# Electrical_Channels.net
KiCad netlist of a schematic drawn in Altium Designer
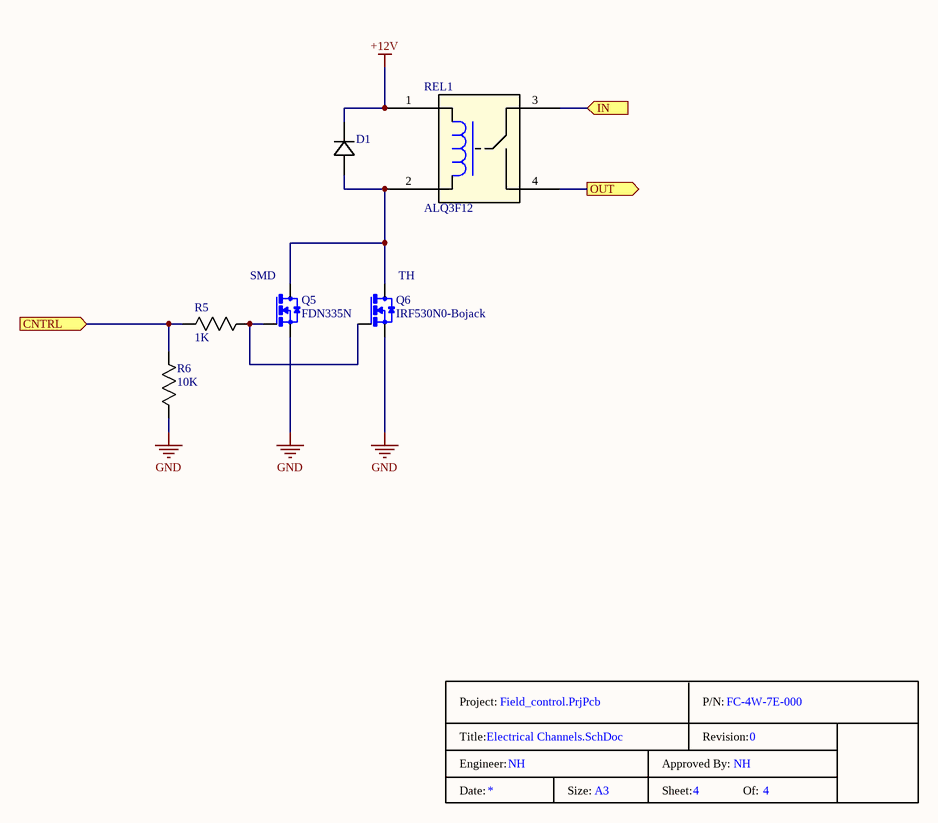
[diagram p0: Electrical Channels.SchDoc]

(export (version "E")
  (design (tool "Eeschema 10.0.6"))
  (components
    (comp (ref "*") (value "Tital_block_1") (libsource (lib "Graphical") (part "Tital_block_1")))
    (comp (ref "D1")
      (value "1N5392")
      (footprint "PCBComponent_1")
      (description "DIODE STANDARD 100V 1.5A DO204AL")
      (fields (field (name "MANUFACTURER") "Vishay General Semiconductor - Diodes Division"))
      (libsource (lib "Diodes") (part "1N5392"))
    )
    (comp (ref "Q5")
      (value "FDN335N")
      (footprint "ON-SEMI SOT 23")
      (description "MOSFET N-CH 20V 1.7A SUPERSOT3")
      (fields (field (name "MANUFACTURER") "onsemi"))
      (libsource (lib "Transistors") (part "FDN335N"))
    )
    (comp (ref "Q6")
      (value "IRF530N0-Bojack")
      (footprint "SOT78(TO220AB)")
      (description "MOSFET N-CH 100V 17A TO220AB")
      (fields (field (name "MANUFACTURER") "Bojack"))
      (libsource (lib "Transistors") (part "IRF530N0-Bojack"))
    )
    (comp (ref "R5")
      (value "1K")
      (footprint "R0603")
      (fields (field (name "MANUFACTURER") "Stackpole Electronics Inc"))
      (libsource (lib "Resistors") (part "RMCF0603FT1K00"))
    )
    (comp (ref "R6")
      (value "10K")
      (footprint "R0603")
      (fields (field (name "MANUFACTURER") "Stackpole Electronics Inc"))
      (libsource (lib "Resistors") (part "RMCF0603FT10K0"))
    )
    (comp (ref "REL1")
      (value "ALQ3F12")
      (footprint "ALQ3F12")
      (fields (field (name "MANUFACTURER") "Panasonic Electric Works"))
      (libsource (lib "Relays_Contactors") (part "ALQ3F12"))
    )
  )
  (nets
    (net (code "1") (name "+12V") (class "Default")
      (node (ref "D1") (pin "1") (pinfunction "C_1") (pintype "passive"))
      (node (ref "REL1") (pin "1") (pinfunction "1_1") (pintype "passive"))
    )
    (net (code "2") (name "/CNTRL") (class "Default")
      (node (ref "R5") (pin "1") (pinfunction "1_1") (pintype "passive"))
      (node (ref "R6") (pin "2") (pinfunction "2_2") (pintype "passive"))
    )
    (net (code "3") (name "/IN") (class "Default")
      (node (ref "REL1") (pin "3") (pinfunction "3_3") (pintype "passive"))
    )
    (net (code "4") (name "/OUT") (class "Default")
      (node (ref "REL1") (pin "4") (pinfunction "4_4") (pintype "passive"))
    )
    (net (code "5") (name "GND") (class "Default")
      (node (ref "Q5") (pin "2") (pinfunction "S_2") (pintype "passive"))
      (node (ref "Q6") (pin "2") (pinfunction "S_2") (pintype "passive"))
      (node (ref "R6") (pin "1") (pinfunction "1_1") (pintype "passive"))
    )
    (net (code "6") (name "Net-(D1-A)") (class "Default")
      (node (ref "D1") (pin "2") (pinfunction "A_2") (pintype "passive"))
      (node (ref "Q5") (pin "3") (pinfunction "D_3") (pintype "passive"))
      (node (ref "Q6") (pin "3") (pinfunction "D_3") (pintype "passive"))
      (node (ref "REL1") (pin "2") (pinfunction "2_2") (pintype "passive"))
    )
    (net (code "7") (name "Net-(Q5-G)") (class "Default")
      (node (ref "Q5") (pin "1") (pinfunction "G_1") (pintype "passive"))
      (node (ref "Q6") (pin "1") (pinfunction "G_1") (pintype "passive"))
      (node (ref "R5") (pin "2") (pinfunction "2_2") (pintype "passive"))
    )
  )
)
